# shield_ESP.net
KiCad netlist of a schematic drawn in EAGLE
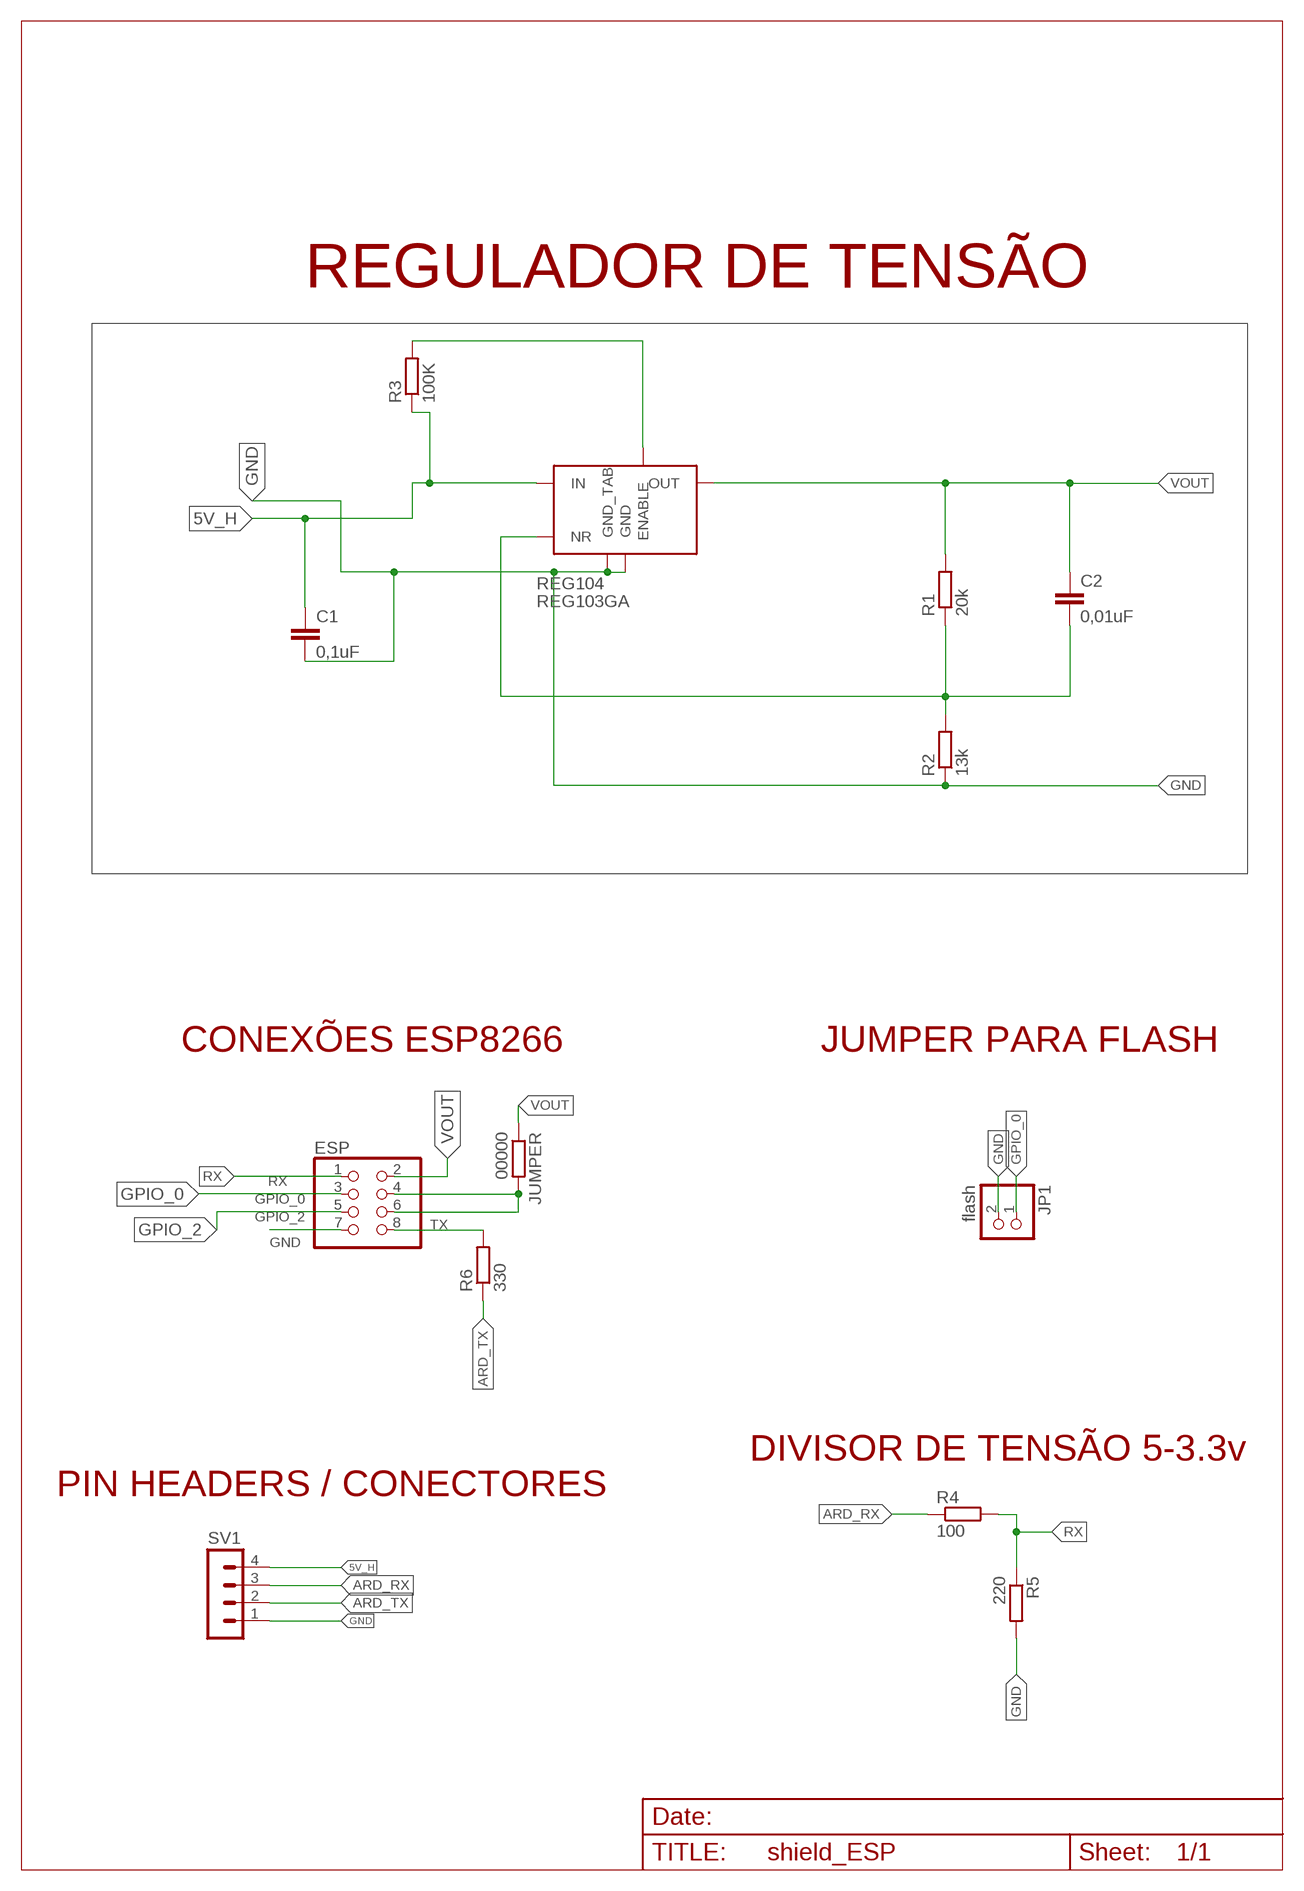
[diagram p0: schematic, sheet 1]

(export (version "E")
  (design (tool "Eeschema 10.0.6"))
  (components
    (comp (ref "C1")
      (value "0,1uF")
      (footprint "eagle-import:C025-025X050")
      (libsource (lib "eagle-import") (part "C-EU025-025X050"))
    )
    (comp (ref "C2")
      (value "0,01uF")
      (footprint "eagle-import:C025-025X050")
      (libsource (lib "eagle-import") (part "C-EU025-025X050"))
    )
    (comp (ref "ESP")
      (value "PINHD-2X4")
      (footprint "eagle-import:2X04")
      (libsource (lib "eagle-import") (part "PINHD-2X4"))
    )
    (comp (ref "JP1")
      (value "flash")
      (footprint "eagle-import:1X02_90")
      (libsource (lib "eagle-import") (part "PINHD-1X2/90"))
    )
    (comp (ref "JUMPER")
      (value "00000")
      (footprint "eagle-import:0207_7")
      (libsource (lib "eagle-import") (part "resistor_R-EU_0207/7"))
    )
    (comp (ref "R1")
      (value "20k")
      (footprint "eagle-import:0207_7")
      (libsource (lib "eagle-import") (part "R-EU_0207/7"))
    )
    (comp (ref "R2")
      (value "13k")
      (footprint "eagle-import:0207_7")
      (libsource (lib "eagle-import") (part "R-EU_0207/7"))
    )
    (comp (ref "R3")
      (value "100K")
      (footprint "eagle-import:0207_7")
      (libsource (lib "eagle-import") (part "R-EU_0207/7"))
    )
    (comp (ref "R4")
      (value "100")
      (footprint "eagle-import:0207_7")
      (libsource (lib "eagle-import") (part "resistor_R-EU_0207/7"))
    )
    (comp (ref "R5")
      (value "220")
      (footprint "eagle-import:0207_7")
      (libsource (lib "eagle-import") (part "resistor_R-EU_0207/7"))
    )
    (comp (ref "R6")
      (value "330")
      (footprint "eagle-import:0207_7")
      (libsource (lib "eagle-import") (part "resistor_R-EU_0207/7"))
    )
    (comp (ref "REG104")
      (value "REG103GA")
      (footprint "eagle-import:SOT223-5")
      (libsource (lib "eagle-import") (part "REG103GA"))
    )
    (comp (ref "SV1")
      (value "MA04-1")
      (footprint "eagle-import:MA04-1")
      (libsource (lib "eagle-import") (part "MA04-1"))
    )
  )
  (nets
    (net (code "1") (name "/TX") (class "Default")
      (node (ref "ESP") (pin "8") (pinfunction "8_8") (pintype "passive"))
      (node (ref "R6") (pin "2") (pinfunction "2_2") (pintype "passive"))
    )
    (net (code "2") (name "5V_H") (class "Default")
      (node (ref "C1") (pin "1") (pinfunction "1_1") (pintype "passive"))
      (node (ref "R3") (pin "1") (pinfunction "1_1") (pintype "passive"))
      (node (ref "REG104") (pin "1") (pinfunction "IN_1") (pintype "bidirectional"))
      (node (ref "SV1") (pin "4") (pinfunction "4_4") (pintype "passive"))
    )
    (net (code "3") (name "ARD_RX") (class "Default")
      (node (ref "R4") (pin "1") (pinfunction "1_1") (pintype "passive"))
      (node (ref "SV1") (pin "3") (pinfunction "3_3") (pintype "passive"))
    )
    (net (code "4") (name "ARD_TX") (class "Default")
      (node (ref "R6") (pin "1") (pinfunction "1_1") (pintype "passive"))
      (node (ref "SV1") (pin "2") (pinfunction "2_2") (pintype "passive"))
    )
    (net (code "5") (name "GND") (class "Default")
      (node (ref "C1") (pin "2") (pinfunction "2_2") (pintype "passive"))
      (node (ref "ESP") (pin "7") (pinfunction "7_7") (pintype "passive"))
      (node (ref "JP1") (pin "2") (pinfunction "2_2") (pintype "passive"))
      (node (ref "R2") (pin "1") (pinfunction "1_1") (pintype "passive"))
      (node (ref "R5") (pin "2") (pinfunction "2_2") (pintype "passive"))
      (node (ref "REG104") (pin "3") (pinfunction "GND_3") (pintype "bidirectional"))
      (node (ref "REG104") (pin "TAB") (pinfunction "GND_TAB_TAB") (pintype "bidirectional"))
      (node (ref "SV1") (pin "1") (pinfunction "1_1") (pintype "passive"))
    )
    (net (code "6") (name "GPIO_0") (class "Default")
      (node (ref "ESP") (pin "3") (pinfunction "3_3") (pintype "passive"))
      (node (ref "JP1") (pin "1") (pinfunction "1_1") (pintype "passive"))
    )
    (net (code "7") (name "GPIO_2") (class "Default")
      (node (ref "ESP") (pin "5") (pinfunction "5_5") (pintype "passive"))
    )
    (net (code "8") (name "Net-(ESP-Pad4)") (class "Default")
      (node (ref "ESP") (pin "4") (pinfunction "4_4") (pintype "passive"))
      (node (ref "ESP") (pin "6") (pinfunction "6_6") (pintype "passive"))
      (node (ref "JUMPER") (pin "2") (pinfunction "2_2") (pintype "passive"))
    )
    (net (code "9") (name "Net-(REG104-ENABLE)") (class "Default")
      (node (ref "R3") (pin "2") (pinfunction "2_2") (pintype "passive"))
      (node (ref "REG104") (pin "5") (pinfunction "ENABLE_5") (pintype "bidirectional"))
    )
    (net (code "10") (name "Net-(REG104-NR)") (class "Default")
      (node (ref "C2") (pin "2") (pinfunction "2_2") (pintype "passive"))
      (node (ref "R1") (pin "1") (pinfunction "1_1") (pintype "passive"))
      (node (ref "R2") (pin "2") (pinfunction "2_2") (pintype "passive"))
      (node (ref "REG104") (pin "4") (pinfunction "NR_4") (pintype "bidirectional"))
    )
    (net (code "11") (name "RX") (class "Default")
      (node (ref "ESP") (pin "1") (pinfunction "1_1") (pintype "passive"))
      (node (ref "R4") (pin "2") (pinfunction "2_2") (pintype "passive"))
      (node (ref "R5") (pin "1") (pinfunction "1_1") (pintype "passive"))
    )
    (net (code "12") (name "VOUT") (class "Default")
      (node (ref "C2") (pin "1") (pinfunction "1_1") (pintype "passive"))
      (node (ref "ESP") (pin "2") (pinfunction "2_2") (pintype "passive"))
      (node (ref "JUMPER") (pin "1") (pinfunction "1_1") (pintype "passive"))
      (node (ref "R1") (pin "2") (pinfunction "2_2") (pintype "passive"))
      (node (ref "REG104") (pin "2") (pinfunction "OUT_2") (pintype "bidirectional"))
    )
  )
)
